# receive.net
KiCad netlist of a schematic drawn in Altium Designer
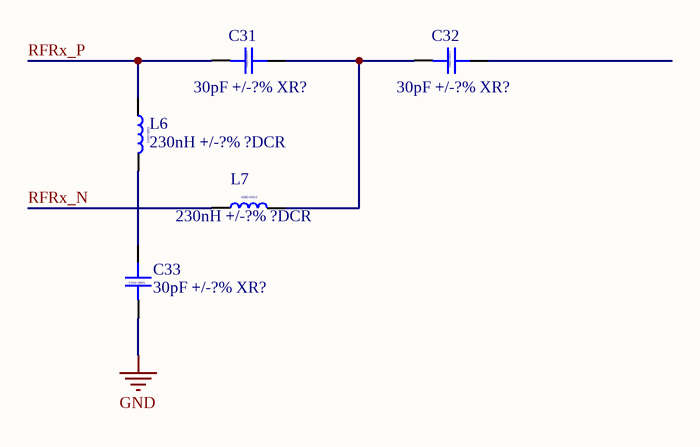
[diagram p0: receive.SchDoc]

(export (version "E")
  (design (tool "Eeschema 10.0.6"))
  (components
    (comp (ref "C31")
      (value "30pF +/-?% XR?")
      (footprint "CAP_0603")
      (description "Capacitor SMD 0603 RATED")
      (libsource (lib "STeRG-Passives-Standard") (part "Capacitor-SMD-0603"))
    )
    (comp (ref "C32")
      (value "30pF +/-?% XR?")
      (footprint "CAP_0603")
      (description "Capacitor SMD 0603 RATED")
      (libsource (lib "STeRG-Passives-Standard") (part "Capacitor-SMD-0603"))
    )
    (comp (ref "C33")
      (value "30pF +/-?% XR?")
      (footprint "CAP_0603")
      (description "Capacitor SMD 0603 RATED")
      (libsource (lib "STeRG-Passives-Standard") (part "Capacitor-SMD-0603"))
    )
    (comp (ref "L6")
      (value "230nH +/-?% ?DCR")
      (footprint "IND_0603")
      (description "Inductor SMD 0603")
      (libsource (lib "STeRG-Passives-Standard") (part "Inductor-SMD-RF-0603"))
    )
    (comp (ref "L7")
      (value "230nH +/-?% ?DCR")
      (footprint "IND_0603")
      (description "Inductor SMD 0603")
      (libsource (lib "STeRG-Passives-Standard") (part "Inductor-SMD-RF-0603"))
    )
  )
  (nets
    (net (code "1") (name "/RFRx_N") (class "Default")
      (node (ref "L7") (pin "1") (pinfunction "1_1") (pintype "passive"))
    )
    (net (code "2") (name "/RFRx_P") (class "Default")
      (node (ref "C31") (pin "1") (pinfunction "1_1") (pintype "passive"))
      (node (ref "L6") (pin "1") (pinfunction "1_1") (pintype "passive"))
    )
    (net (code "3") (name "GND") (class "Default")
      (node (ref "C33") (pin "1") (pinfunction "1_1") (pintype "passive"))
    )
    (net (code "4") (name "Net-(C31-Pad2)") (class "Default")
      (node (ref "C31") (pin "2") (pinfunction "2_2") (pintype "passive"))
      (node (ref "C32") (pin "1") (pinfunction "1_1") (pintype "passive"))
      (node (ref "L7") (pin "2") (pinfunction "2_2") (pintype "passive"))
    )
    (net (code "5") (name "Net-(C33-Pad2)") (class "Default")
      (node (ref "C33") (pin "2") (pinfunction "2_2") (pintype "passive"))
      (node (ref "L6") (pin "2") (pinfunction "2_2") (pintype "passive"))
    )
    (net (code "6") (name "unconnected-(C32-Pad2)") (class "Default")
      (node (ref "C32") (pin "2") (pinfunction "2_2") (pintype "passive"))
    )
  )
)
